# 06_LEDS.net
KiCad netlist of a schematic drawn in Altium Designer
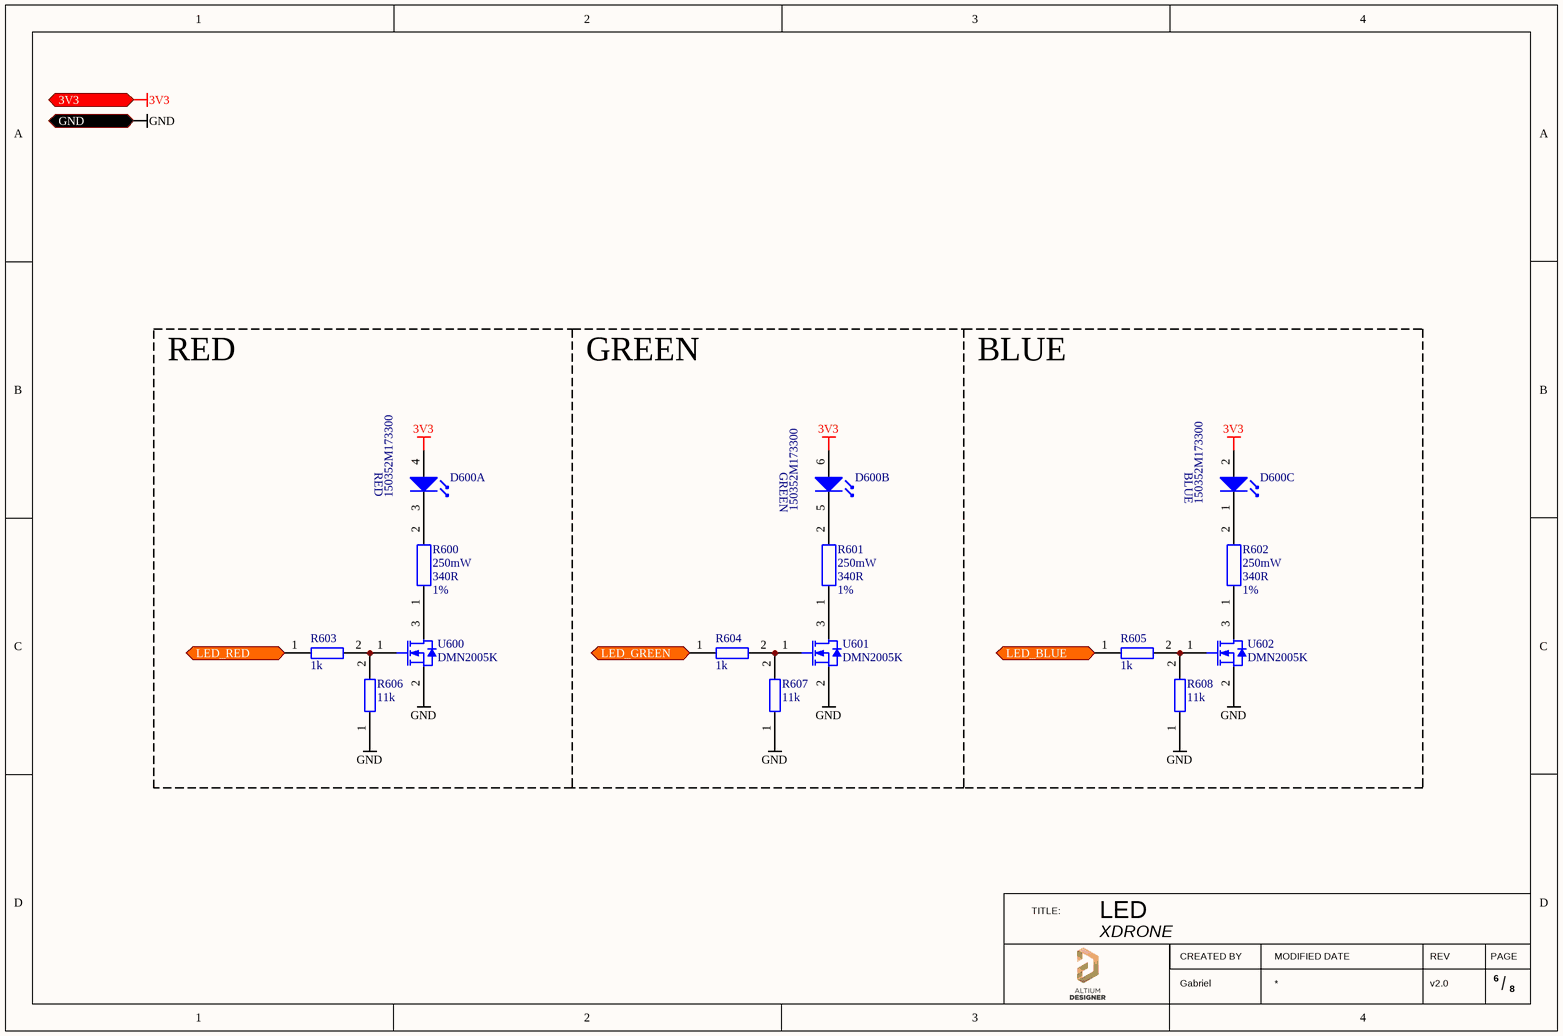
[diagram p0: 06_LEDS.SchDoc]

(export (version "E")
  (design (tool "Eeschema 10.0.6"))
  (components
    (comp (ref "D600")
      (value "LED_PLCC6_RGB_150352M173300")
      (footprint "6-PLCC")
      (description "CBI LED RGB PLCC6 150352M173300")
      (fields (field (name "MANUFACTURER") "WURTH") (field (name "MANUFACTURER REFERENCE") "150352M173300"))
      (libsource (lib "Semiconductor") (part "LED_PLCC6_RGB_150352M173300"))
    )
    (comp (ref "R600")
      (value "340R")
      (footprint "RES_0805")
      (description "RESISTOR SMD 0805 340R 1/4W 1% METAL")
      (fields
        (field (name "MANUFACTURER") "KOA")
        (field (name "MAX POWER DISSIPATION") "250mW")
        (field (name "TOLERANCE") "1%")
        (field (name "Comment") "RC_0805_340R_1/4W_1%_M")
      )
      (libsource (lib "Resistors") (part "RC_0805_340R_1/4W_1%_M"))
    )
    (comp (ref "R601")
      (value "340R")
      (footprint "RES_0805")
      (description "RESISTOR SMD 0805 340R 1/4W 1% METAL")
      (fields
        (field (name "MANUFACTURER") "KOA")
        (field (name "MAX POWER DISSIPATION") "250mW")
        (field (name "TOLERANCE") "1%")
        (field (name "Comment") "RC_0805_340R_1/4W_1%_M")
      )
      (libsource (lib "Resistors") (part "RC_0805_340R_1/4W_1%_M"))
    )
    (comp (ref "R602")
      (value "340R")
      (footprint "RES_0805")
      (description "RESISTOR SMD 0805 340R 1/4W 1% METAL")
      (fields
        (field (name "MANUFACTURER") "KOA")
        (field (name "MAX POWER DISSIPATION") "250mW")
        (field (name "TOLERANCE") "1%")
        (field (name "Comment") "RC_0805_340R_1/4W_1%_M")
      )
      (libsource (lib "Resistors") (part "RC_0805_340R_1/4W_1%_M"))
    )
    (comp (ref "R603")
      (value "1k")
      (footprint "RES_0402")
      (description "RESISTOR 1k 1% 0402 RC0402FR-071KL")
      (fields (field (name "TOLERANCE") "1%") (field (name "MANUFACTURER") "YAGEO"))
      (libsource (lib "Resistors") (part "RES_1k_1%_0402_RC0402FR-071KL"))
    )
    (comp (ref "R604")
      (value "1k")
      (footprint "RES_0402")
      (description "RESISTOR 1k 1% 0402 RC0402FR-071KL")
      (fields (field (name "TOLERANCE") "1%") (field (name "MANUFACTURER") "YAGEO"))
      (libsource (lib "Resistors") (part "RES_1k_1%_0402_RC0402FR-071KL"))
    )
    (comp (ref "R605")
      (value "1k")
      (footprint "RES_0402")
      (description "RESISTOR 1k 1% 0402 RC0402FR-071KL")
      (fields (field (name "TOLERANCE") "1%") (field (name "MANUFACTURER") "YAGEO"))
      (libsource (lib "Resistors") (part "RES_1k_1%_0402_RC0402FR-071KL"))
    )
    (comp (ref "R606")
      (value "11k")
      (footprint "RES_0402")
      (description "RESISTOR 11k 5% 0402 ERJ-2GEJ113X")
      (fields (field (name "TOLERANCE") "5%") (field (name "MANUFACTURER") "PANASONIC"))
      (libsource (lib "Resistors") (part "RES_11k_5%_0402_ERJ-2GEJ113X"))
    )
    (comp (ref "R607")
      (value "11k")
      (footprint "RES_0402")
      (description "RESISTOR 11k 5% 0402 ERJ-2GEJ113X")
      (fields (field (name "TOLERANCE") "5%") (field (name "MANUFACTURER") "PANASONIC"))
      (libsource (lib "Resistors") (part "RES_11k_5%_0402_ERJ-2GEJ113X"))
    )
    (comp (ref "R608")
      (value "11k")
      (footprint "RES_0402")
      (description "RESISTOR 11k 5% 0402 ERJ-2GEJ113X")
      (fields (field (name "TOLERANCE") "5%") (field (name "MANUFACTURER") "PANASONIC"))
      (libsource (lib "Resistors") (part "RES_11k_5%_0402_ERJ-2GEJ113X"))
    )
    (comp (ref "U600")
      (value "MOS_N_1G_0.3A_DMN2005K")
      (footprint "SOT-23")
      (description "TRANSISTOR MOSFET N 0.3A 20V")
      (fields (field (name "MANUFACTURER") "DIODES INC") (field (name "MANUFACTURER REFERENCE") "DMN2005K"))
      (libsource (lib "Semiconductor") (part "MOS_N_1G_0.3A_DMN2005K"))
    )
    (comp (ref "U601")
      (value "MOS_N_1G_0.3A_DMN2005K")
      (footprint "SOT-23")
      (description "TRANSISTOR MOSFET N 0.3A 20V")
      (fields (field (name "MANUFACTURER") "DIODES INC") (field (name "MANUFACTURER REFERENCE") "DMN2005K"))
      (libsource (lib "Semiconductor") (part "MOS_N_1G_0.3A_DMN2005K"))
    )
    (comp (ref "U602")
      (value "MOS_N_1G_0.3A_DMN2005K")
      (footprint "SOT-23")
      (description "TRANSISTOR MOSFET N 0.3A 20V")
      (fields (field (name "MANUFACTURER") "DIODES INC") (field (name "MANUFACTURER REFERENCE") "DMN2005K"))
      (libsource (lib "Semiconductor") (part "MOS_N_1G_0.3A_DMN2005K"))
    )
  )
  (nets
    (net (code "1") (name "/LED_BLUE") (class "Default")
      (node (ref "R605") (pin "1") (pinfunction "1_1") (pintype "passive"))
    )
    (net (code "2") (name "/LED_GREEN") (class "Default")
      (node (ref "R604") (pin "1") (pinfunction "1_1") (pintype "passive"))
    )
    (net (code "3") (name "/LED_RED") (class "Default")
      (node (ref "R603") (pin "1") (pinfunction "1_1") (pintype "passive"))
    )
    (net (code "4") (name "3V3") (class "Default")
      (node (ref "D600") (pin "2") (pinfunction "AB_2") (pintype "passive"))
      (node (ref "D600") (pin "4") (pinfunction "AR_4") (pintype "passive"))
      (node (ref "D600") (pin "6") (pinfunction "AG_6") (pintype "passive"))
    )
    (net (code "5") (name "GND") (class "Default")
      (node (ref "R606") (pin "1") (pinfunction "1_1") (pintype "passive"))
      (node (ref "R607") (pin "1") (pinfunction "1_1") (pintype "passive"))
      (node (ref "R608") (pin "1") (pinfunction "1_1") (pintype "passive"))
      (node (ref "U600") (pin "2") (pinfunction "S_2") (pintype "passive"))
      (node (ref "U601") (pin "2") (pinfunction "S_2") (pintype "passive"))
      (node (ref "U602") (pin "2") (pinfunction "S_2") (pintype "passive"))
    )
    (net (code "6") (name "Net-(D600A-KR)") (class "Default")
      (node (ref "D600") (pin "3") (pinfunction "KR_3") (pintype "passive"))
      (node (ref "R600") (pin "2") (pinfunction "2_2") (pintype "passive"))
    )
    (net (code "7") (name "Net-(D600B-KG)") (class "Default")
      (node (ref "D600") (pin "5") (pinfunction "KG_5") (pintype "passive"))
      (node (ref "R601") (pin "2") (pinfunction "2_2") (pintype "passive"))
    )
    (net (code "8") (name "Net-(D600C-KB)") (class "Default")
      (node (ref "D600") (pin "1") (pinfunction "KB_1") (pintype "passive"))
      (node (ref "R602") (pin "2") (pinfunction "2_2") (pintype "passive"))
    )
    (net (code "9") (name "Net-(U600-D)") (class "Default")
      (node (ref "R600") (pin "1") (pinfunction "1_1") (pintype "passive"))
      (node (ref "U600") (pin "3") (pinfunction "D_3") (pintype "passive"))
    )
    (net (code "10") (name "Net-(U600-G)") (class "Default")
      (node (ref "R603") (pin "2") (pinfunction "2_2") (pintype "passive"))
      (node (ref "R606") (pin "2") (pinfunction "2_2") (pintype "passive"))
      (node (ref "U600") (pin "1") (pinfunction "G_1") (pintype "passive"))
    )
    (net (code "11") (name "Net-(U601-D)") (class "Default")
      (node (ref "R601") (pin "1") (pinfunction "1_1") (pintype "passive"))
      (node (ref "U601") (pin "3") (pinfunction "D_3") (pintype "passive"))
    )
    (net (code "12") (name "Net-(U601-G)") (class "Default")
      (node (ref "R604") (pin "2") (pinfunction "2_2") (pintype "passive"))
      (node (ref "R607") (pin "2") (pinfunction "2_2") (pintype "passive"))
      (node (ref "U601") (pin "1") (pinfunction "G_1") (pintype "passive"))
    )
    (net (code "13") (name "Net-(U602-D)") (class "Default")
      (node (ref "R602") (pin "1") (pinfunction "1_1") (pintype "passive"))
      (node (ref "U602") (pin "3") (pinfunction "D_3") (pintype "passive"))
    )
    (net (code "14") (name "Net-(U602-G)") (class "Default")
      (node (ref "R605") (pin "2") (pinfunction "2_2") (pintype "passive"))
      (node (ref "R608") (pin "2") (pinfunction "2_2") (pintype "passive"))
      (node (ref "U602") (pin "1") (pinfunction "G_1") (pintype "passive"))
    )
  )
)
